# Wiring.net
KiCad netlist of a schematic drawn in Altium Designer
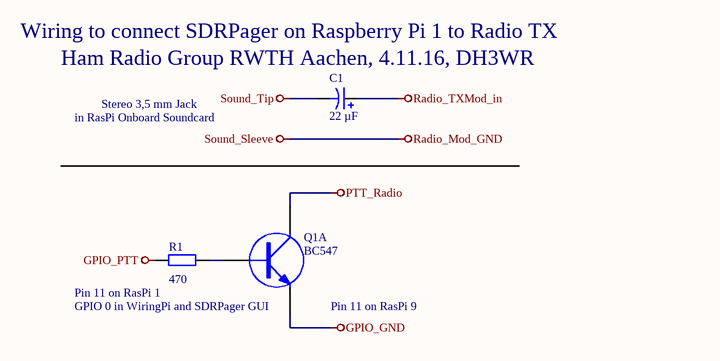
[diagram p0: Wiring.SchDoc]

(export (version "E")
  (design (tool "Eeschema 10.0.6"))
  (components
    (comp (ref "C1")
      (value "22 µF")
      (footprint "RB7.6-15")
      (description "Polarized Capacitor (Radial)")
      (fields (field (name "Comment") "Cap Pol1") (field (name "PUBLISHER") "Altium Limited"))
      (libsource (lib "Miscellaneous Devices") (part "Cap Pol1"))
    )
    (comp (ref "Q1")
      (value "BC547")
      (footprint "SOT363")
      (description "NPN Transistor")
      (libsource (lib "FKA_DXP_Source") (part "BC847S"))
    )
    (comp (ref "R1")
      (value "470")
      (footprint "AXIAL-0.4")
      (description "Resistor")
      (fields (field (name "Comment") "Res2") (field (name "PUBLISHER") "Altium Limited"))
      (libsource (lib "Miscellaneous Devices") (part "Res2"))
    )
  )
  (nets
    (net (code "1") (name "GPIO_GND") (class "Default")
      (node (ref "Q1") (pin "1") (pinfunction "E1_1") (pintype "passive"))
    )
    (net (code "2") (name "GPIO_PTT") (class "Default")
      (node (ref "R1") (pin "1") (pinfunction "1_1") (pintype "passive"))
    )
    (net (code "3") (name "Net-(Q1A-B1)") (class "Default")
      (node (ref "Q1") (pin "2") (pinfunction "B1_2") (pintype "passive"))
      (node (ref "R1") (pin "2") (pinfunction "2_2") (pintype "passive"))
    )
    (net (code "4") (name "PTT_Radio") (class "Default")
      (node (ref "Q1") (pin "6") (pinfunction "C1_6") (pintype "passive"))
    )
    (net (code "6") (name "Radio_TXMod_in") (class "Default")
      (node (ref "C1") (pin "1") (pinfunction "1_1") (pintype "passive"))
    )
    (net (code "7") (name "Sound_Tip") (class "Default")
      (node (ref "C1") (pin "2") (pinfunction "2_2") (pintype "passive"))
    )
  )
)
